# MCU.net
KiCad netlist of a schematic drawn in Altium Designer
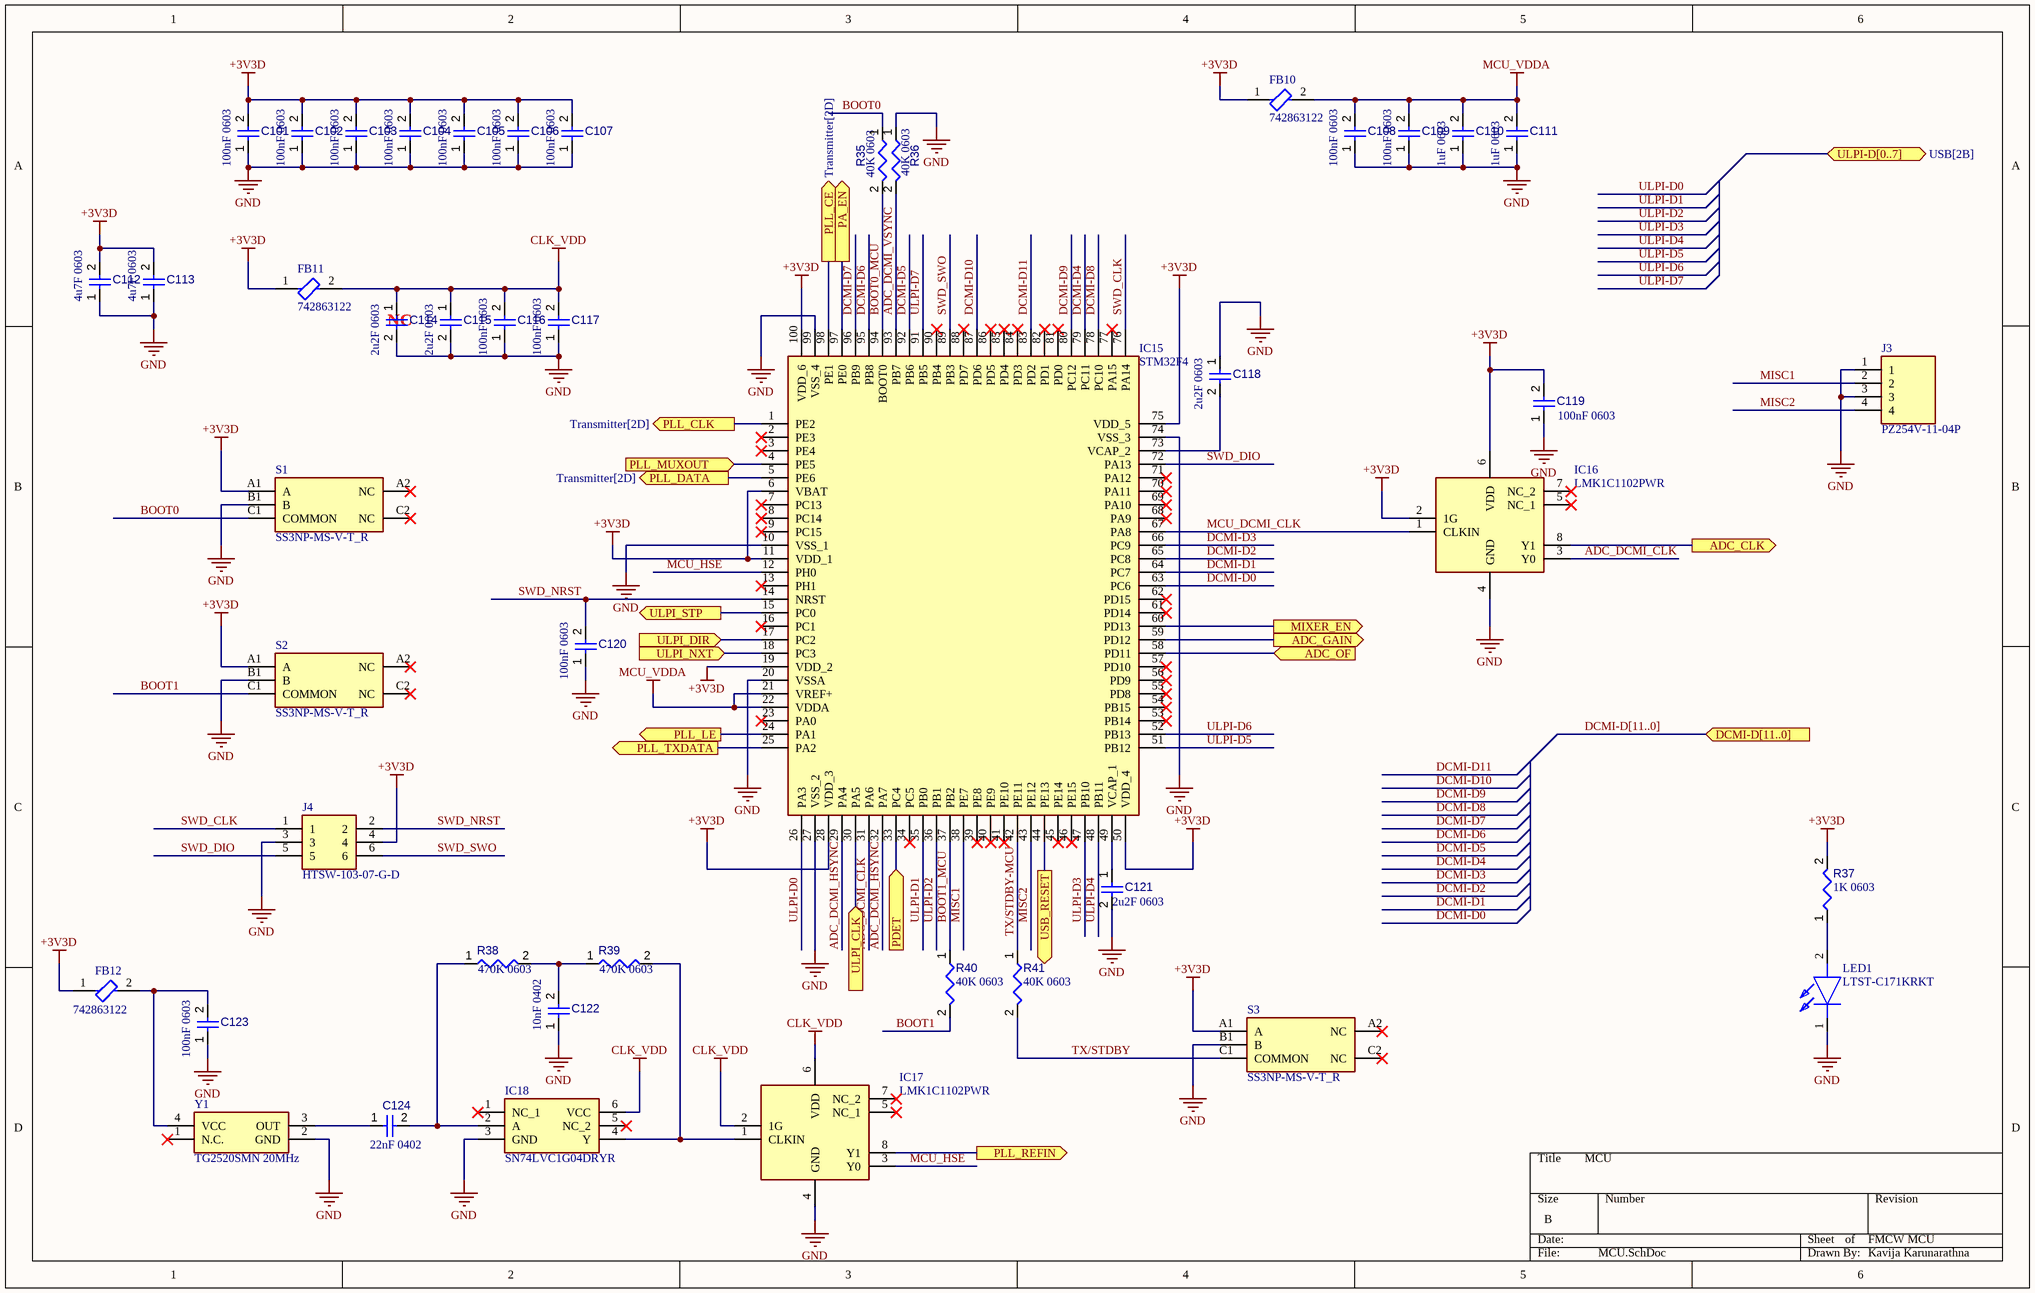
[diagram p0: MCU.SchDoc]

(export (version "E")
  (design (tool "Eeschema 10.0.6"))
  (components
    (comp (ref "C101")
      (value "100nF 0603")
      (footprint "CAPC0603(1608)100_L")
      (description "Chip Capacitor, 1µF +/-0.1%, 25V, 0603, Thickness 1 mm")
      (fields (field (name "TOLERANCE") "20%") (field (name "MANUFACTURER PART NO") "0603X104K250CT"))
      (libsource (lib "Kavija Karunarathna") (part "CAP-NP-2"))
    )
    (comp (ref "C102")
      (value "100nF 0603")
      (footprint "CAPC0603(1608)100_L")
      (description "Chip Capacitor, 1µF +/-0.1%, 25V, 0603, Thickness 1 mm")
      (fields (field (name "TOLERANCE") "20%") (field (name "MANUFACTURER PART NO") "0603X104K250CT"))
      (libsource (lib "Kavija Karunarathna") (part "CAP-NP-2"))
    )
    (comp (ref "C103")
      (value "100nF 0603")
      (footprint "CAPC0603(1608)100_L")
      (description "Chip Capacitor, 1µF +/-0.1%, 25V, 0603, Thickness 1 mm")
      (fields (field (name "TOLERANCE") "20%") (field (name "MANUFACTURER PART NO") "0603X104K250CT"))
      (libsource (lib "Kavija Karunarathna") (part "CAP-NP-2"))
    )
    (comp (ref "C104")
      (value "100nF 0603")
      (footprint "CAPC0603(1608)100_L")
      (description "Chip Capacitor, 1µF +/-0.1%, 25V, 0603, Thickness 1 mm")
      (fields (field (name "TOLERANCE") "20%") (field (name "MANUFACTURER PART NO") "0603X104K250CT"))
      (libsource (lib "Kavija Karunarathna") (part "CAP-NP-2"))
    )
    (comp (ref "C105")
      (value "100nF 0603")
      (footprint "CAPC0603(1608)100_L")
      (description "Chip Capacitor, 1µF +/-0.1%, 25V, 0603, Thickness 1 mm")
      (fields (field (name "TOLERANCE") "20%") (field (name "MANUFACTURER PART NO") "0603X104K250CT"))
      (libsource (lib "Kavija Karunarathna") (part "CAP-NP-2"))
    )
    (comp (ref "C106")
      (value "100nF 0603")
      (footprint "CAPC0603(1608)100_L")
      (description "Chip Capacitor, 1µF +/-0.1%, 25V, 0603, Thickness 1 mm")
      (fields (field (name "TOLERANCE") "20%") (field (name "MANUFACTURER PART NO") "0603X104K250CT"))
      (libsource (lib "Kavija Karunarathna") (part "CAP-NP-2"))
    )
    (comp (ref "C107")
      (value "100nF 0603")
      (footprint "CAPC0603(1608)100_L")
      (description "Chip Capacitor, 1µF +/-0.1%, 25V, 0603, Thickness 1 mm")
      (fields (field (name "TOLERANCE") "20%") (field (name "MANUFACTURER PART NO") "0603X104K250CT"))
      (libsource (lib "Kavija Karunarathna") (part "CAP-NP-2"))
    )
    (comp (ref "C108")
      (value "100nF 0603")
      (footprint "CAPC0603(1608)100_L")
      (description "Chip Capacitor, 1µF +/-0.1%, 25V, 0603, Thickness 1 mm")
      (fields (field (name "TOLERANCE") "20%") (field (name "MANUFACTURER PART NO") "0603X104K250CT"))
      (libsource (lib "Kavija Karunarathna") (part "CAP-NP-2"))
    )
    (comp (ref "C109")
      (value "100nF 0603")
      (footprint "CAPC0603(1608)100_L")
      (description "Chip Capacitor, 1µF +/-0.1%, 25V, 0603, Thickness 1 mm")
      (fields (field (name "TOLERANCE") "20%") (field (name "MANUFACTURER PART NO") "0603X104K250CT"))
      (libsource (lib "Kavija Karunarathna") (part "CAP-NP-2"))
    )
    (comp (ref "C110")
      (value "1uF 0603")
      (footprint "CAPC0603(1608)100_L")
      (description "Chip Capacitor, 1µF +/-0.1%, 25V, 0603, Thickness 1 mm")
      (fields (field (name "TOLERANCE") "20%") (field (name "MANUFACTURER PART NO") "0603YC105KAZ2A"))
      (libsource (lib "Kavija Karunarathna") (part "CAP-NP-2"))
    )
    (comp (ref "C111")
      (value "1uF 0603")
      (footprint "CAPC0603(1608)100_L")
      (description "Chip Capacitor, 1µF +/-0.1%, 25V, 0603, Thickness 1 mm")
      (fields (field (name "TOLERANCE") "20%") (field (name "MANUFACTURER PART NO") "0603YC105KAZ2A"))
      (libsource (lib "Kavija Karunarathna") (part "CAP-NP-2"))
    )
    (comp (ref "C112")
      (value "4u7F 0603")
      (footprint "CAPC0603(1608)100_L")
      (description "Chip Capacitor, 1µF +/-0.1%, 25V, 0603, Thickness 1 mm")
      (fields (field (name "TOLERANCE") "20%") (field (name "MANUFACTURER PART NO") "C0603C475K8PAC7867"))
      (libsource (lib "Kavija Karunarathna") (part "CAP-NP-2"))
    )
    (comp (ref "C113")
      (value "4u7F 0603")
      (footprint "CAPC0603(1608)100_L")
      (description "Chip Capacitor, 1µF +/-0.1%, 25V, 0603, Thickness 1 mm")
      (fields (field (name "TOLERANCE") "20%") (field (name "MANUFACTURER PART NO") "C0603C475K8PAC7867"))
      (libsource (lib "Kavija Karunarathna") (part "CAP-NP-2"))
    )
    (comp (ref "C114")
      (value "2u2F 0603")
      (footprint "CAPC0603(1608)100_L")
      (description "Multilayer Ceramic Capacitors MLCC - SMD/SMT 0603 10nF 16volts X7R 10%")
      (fields (field (name "TOLERANCE") "20%") (field (name "MANUFACTURER PART NO") "VJ0603G225KXQCW1BC"))
      (libsource (lib "Kavija Karunarathna") (part "CAP-NP-2"))
    )
    (comp (ref "C115")
      (value "2u2F 0603")
      (footprint "CAPC0603(1608)100_L")
      (description "Multilayer Ceramic Capacitors MLCC - SMD/SMT 0603 10nF 16volts X7R 10%")
      (fields (field (name "TOLERANCE") "20%") (field (name "MANUFACTURER PART NO") "VJ0603G225KXQCW1BC"))
      (libsource (lib "Kavija Karunarathna") (part "CAP-NP-2"))
    )
    (comp (ref "C116")
      (value "100nF 0603")
      (footprint "CAPC0603(1608)100_L")
      (description "Chip Capacitor, 1µF +/-0.1%, 25V, 0603, Thickness 1 mm")
      (fields (field (name "TOLERANCE") "20%") (field (name "MANUFACTURER PART NO") "0603X104K250CT"))
      (libsource (lib "Kavija Karunarathna") (part "CAP-NP-2"))
    )
    (comp (ref "C117")
      (value "100nF 0603")
      (footprint "CAPC0603(1608)100_L")
      (description "Chip Capacitor, 1µF +/-0.1%, 25V, 0603, Thickness 1 mm")
      (fields (field (name "TOLERANCE") "20%") (field (name "MANUFACTURER PART NO") "0603X104K250CT"))
      (libsource (lib "Kavija Karunarathna") (part "CAP-NP-2"))
    )
    (comp (ref "C118")
      (value "2u2F 0603")
      (footprint "CAPC0603(1608)100_L")
      (description "Multilayer Ceramic Capacitors MLCC - SMD/SMT 0603 10nF 16volts X7R 10%")
      (fields (field (name "TOLERANCE") "20%") (field (name "MANUFACTURER PART NO") "VJ0603G225KXQCW1BC"))
      (libsource (lib "Kavija Karunarathna") (part "CAP-NP-2"))
    )
    (comp (ref "C119")
      (value "100nF 0603")
      (footprint "CAPC0603(1608)100_L")
      (description "Chip Capacitor, 1µF +/-0.1%, 25V, 0603, Thickness 1 mm")
      (fields (field (name "TOLERANCE") "20%") (field (name "MANUFACTURER PART NO") "0603X104K250CT"))
      (libsource (lib "Kavija Karunarathna") (part "CAP-NP-2"))
    )
    (comp (ref "C120")
      (value "100nF 0603")
      (footprint "CAPC0603(1608)100_L")
      (description "Chip Capacitor, 1µF +/-0.1%, 25V, 0603, Thickness 1 mm")
      (fields (field (name "TOLERANCE") "20%") (field (name "MANUFACTURER PART NO") "0603X104K250CT"))
      (libsource (lib "Kavija Karunarathna") (part "CAP-NP-2"))
    )
    (comp (ref "C121")
      (value "2u2F 0603")
      (footprint "CAPC0603(1608)100_L")
      (description "Multilayer Ceramic Capacitors MLCC - SMD/SMT 0603 10nF 16volts X7R 10%")
      (fields (field (name "TOLERANCE") "20%") (field (name "MANUFACTURER PART NO") "VJ0603G225KXQCW1BC"))
      (libsource (lib "Kavija Karunarathna") (part "CAP-NP-2"))
    )
    (comp (ref "C122")
      (value "10nF 0402")
      (footprint "CAPC0402(1005)60_L")
      (description "Multilayer Ceramic Capacitors MLCC - SMD/SMT 50 V 10 pF C0G 0402 1%")
      (fields (field (name "TOLERANCE") "20%") (field (name "MANUFACTURER PART NO") "VJ0402Y103JXJAC"))
      (libsource (lib "Kavija Karunarathna") (part "CAP-NP-2"))
    )
    (comp (ref "C123")
      (value "100nF 0603")
      (footprint "CAPC0603(1608)100_L")
      (description "Chip Capacitor, 1µF +/-0.1%, 25V, 0603, Thickness 1 mm")
      (fields (field (name "TOLERANCE") "20%") (field (name "MANUFACTURER PART NO") "0603X104K250CT"))
      (libsource (lib "Kavija Karunarathna") (part "CAP-NP-2"))
    )
    (comp (ref "C124")
      (value "22nF 0402")
      (footprint "CAPC0402(1005)60_L")
      (description "Multilayer Ceramic Capacitors MLCC - SMD/SMT 50 V 3 pF 0.1 pF C0G (NP0) 0402 - 55 C + 125 C")
      (fields (field (name "TOLERANCE") "20%") (field (name "MANUFACTURER PART NO") "GRM155R71E223KA61D"))
      (libsource (lib "Kavija Karunarathna") (part "CAP-NP-2"))
    )
    (comp (ref "FB10")
      (value "742863122")
      (footprint "FB-0603")
      (description "FERRITE BEAD 0603")
      (fields (field (name "MOUSER PART NO") "710-742863122"))
      (libsource (lib "SchLib") (part "742792662-FB"))
    )
    (comp (ref "FB11")
      (value "742863122")
      (footprint "FB-0603")
      (description "FERRITE BEAD 0603")
      (fields (field (name "MOUSER PART NO") "710-742863122"))
      (libsource (lib "SchLib") (part "742792662-FB"))
    )
    (comp (ref "FB12")
      (value "742863122")
      (footprint "FB-0603")
      (description "FERRITE BEAD 0603")
      (fields (field (name "MOUSER PART NO") "710-742863122"))
      (libsource (lib "SchLib") (part "742792662-FB"))
    )
    (comp (ref "IC15")
      (value "STM32F4")
      (footprint "SamacSys:QFP50P1600X1600X160-100N")
      (description "Integrated Circuit")
      (fields
        (field (name "MANUFACTURER PART NO") "STM32F429VET6TR")
        (field (name "MOUSER PART NO") "511-STM32F429VET6TR")
      )
      (libsource (lib "SchLib") (part "STM32F429VET6TR"))
    )
    (comp (ref "IC16")
      (value "LMK1C1102PWR")
      (footprint "SOP65P640X120-8N")
      (description "Integrated Circuit")
      (fields (field (name "MOUSER PART NO") "595-LMK1C1102PWR"))
      (libsource (lib "SchLib") (part "LMK1C1102PWR"))
    )
    (comp (ref "IC17")
      (value "LMK1C1102PWR")
      (footprint "SOP65P640X120-8N")
      (description "Integrated Circuit")
      (fields (field (name "MOUSER PART NO") "595-LMK1C1102PWR"))
      (libsource (lib "SchLib") (part "LMK1C1102PWR"))
    )
    (comp (ref "IC18")
      (value "SN74LVC1G04DRYR")
      (footprint "TPS3420DDRYR")
      (description "Integrated Circuit")
      (fields
        (field (name "MANUFACTURER PART NO") "SN74LVC1G04DRY2")
        (field (name "MOUSER PART NO") "595-SN74LVC1G04DRY2")
      )
      (libsource (lib "SchLib") (part "SN74LVC1G04DRYR"))
    )
    (comp (ref "J3")
      (value "PZ254V-11-04P")
      (footprint "SamacSys:HDRV4W64P0X254_1X4_1016X250X890P")
      (description "Connector")
      (libsource (lib "*") (part "PZ254V-11-04P"))
    )
    (comp (ref "J4")
      (value "HTSW-103-07-G-D")
      (footprint "HDRV6W64P254_2X3_762X508X838P")
      (description "Connector")
      (fields (field (name "MOUSER PART NO") "200-HTSW10307GD"))
      (libsource (lib "SchLib") (part "HTSW-103-07-G-D"))
    )
    (comp (ref "LED1")
      (value "LTST-C171KRKT")
      (footprint "LEDM2012X90N")
      (description "LED")
      (fields (field (name "MOUSER PART NO") "859-LTST-C171KRKT"))
      (libsource (lib "SchLib") (part "LTST-C171KRKT"))
    )
    (comp (ref "R35")
      (value "40K 0603")
      (footprint "RESC0603(1608)_L")
      (description "Thin Film Resistors - SMD 0603 40kOhms 0.1% 25 PPM 100mW AECQ200")
      (fields (field (name "POWER") "100mW") (field (name "TOLERANCE") "5%"))
      (libsource (lib "Kavija Karunarathna") (part "120R3J"))
    )
    (comp (ref "R36")
      (value "40K 0603")
      (footprint "RESC0603(1608)_L")
      (description "Thin Film Resistors - SMD 0603 40kOhms 0.1% 25 PPM 100mW AECQ200")
      (fields (field (name "POWER") "100mW") (field (name "TOLERANCE") "5%"))
      (libsource (lib "Kavija Karunarathna") (part "120R3J"))
    )
    (comp (ref "R37")
      (value "1K 0603")
      (footprint "RESC0603(1608)_L")
      (description "Thin Film Resistors - SMD RN 0603 8K06 0.1% 10PPM")
      (fields (field (name "POWER") "100mW") (field (name "TOLERANCE") "5%"))
      (libsource (lib "Kavija Karunarathna") (part "120R3J"))
    )
    (comp (ref "R38")
      (value "470K 0603")
      (footprint "RESC0603(1608)_L")
      (description "Thick Film Resistors - SMD General Purpose Chip Resistor 0603, 200Ohms, 1%, 1/10W")
      (fields (field (name "POWER") "100mW") (field (name "TOLERANCE") "5%"))
      (libsource (lib "Kavija Karunarathna") (part "120R3J"))
    )
    (comp (ref "R39")
      (value "470K 0603")
      (footprint "RESC0603(1608)_L")
      (description "Thick Film Resistors - SMD General Purpose Chip Resistor 0603, 200Ohms, 1%, 1/10W")
      (fields (field (name "POWER") "100mW") (field (name "TOLERANCE") "5%"))
      (libsource (lib "Kavija Karunarathna") (part "120R3J"))
    )
    (comp (ref "R40")
      (value "40K 0603")
      (footprint "RESC0603(1608)_L")
      (description "Thin Film Resistors - SMD 0603 40kOhms 0.1% 25 PPM 100mW AECQ200")
      (fields (field (name "POWER") "100mW") (field (name "TOLERANCE") "5%"))
      (libsource (lib "Kavija Karunarathna") (part "120R3J"))
    )
    (comp (ref "R41")
      (value "40K 0603")
      (footprint "RESC0603(1608)_L")
      (description "Thin Film Resistors - SMD 0603 40kOhms 0.1% 25 PPM 100mW AECQ200")
      (fields (field (name "POWER") "100mW") (field (name "TOLERANCE") "5%"))
      (libsource (lib "Kavija Karunarathna") (part "120R3J"))
    )
    (comp (ref "S1")
      (value "SS3NP-MS-V-T_R")
      (footprint "SS3NPMSVTR")
      (description "Switch")
      (fields
        (field (name "MANUFACTURER PART NO") "SS3NP-MS-V-T/R")
        (field (name "MOUSER PART NO") "113-SS3NPMSVT/R")
      )
      (libsource (lib "SchLib") (part "SS3NP-MS-V-T_R"))
    )
    (comp (ref "S2")
      (value "SS3NP-MS-V-T_R")
      (footprint "SS3NPMSVTR")
      (description "Switch")
      (fields
        (field (name "MANUFACTURER PART NO") "SS3NP-MS-V-T/R")
        (field (name "MOUSER PART NO") "113-SS3NPMSVT/R")
      )
      (libsource (lib "SchLib") (part "SS3NP-MS-V-T_R"))
    )
    (comp (ref "S3")
      (value "SS3NP-MS-V-T_R")
      (footprint "SS3NPMSVTR")
      (description "Switch")
      (fields
        (field (name "MANUFACTURER PART NO") "SS3NP-MS-V-T/R")
        (field (name "MOUSER PART NO") "113-SS3NPMSVT/R")
      )
      (libsource (lib "SchLib") (part "SS3NP-MS-V-T_R"))
    )
    (comp (ref "Y1")
      (value "TG2520SMN 20MHz")
      (footprint "TG2520SMN200000MECGNNM3")
      (description "Crystal or Oscillator")
      (fields
        (field (name "MANUFACTURER PART NO") "TG2520SMN 20.0000M-MCGNNM3")
        (field (name "MOUSER PART NO") "732-TG252S2MCGNNM3")
      )
      (libsource (lib "SchLib") (part "TG2520SMN 20MHz"))
    )
  )
  (nets
    (net (code "1") (name "+3V3D") (class "Default")
      (node (ref "C101") (pin "2") (pinfunction "2_2") (pintype "passive"))
      (node (ref "C102") (pin "2") (pinfunction "2_2") (pintype "passive"))
      (node (ref "C103") (pin "2") (pinfunction "2_2") (pintype "passive"))
      (node (ref "C104") (pin "2") (pinfunction "2_2") (pintype "passive"))
      (node (ref "C105") (pin "2") (pinfunction "2_2") (pintype "passive"))
      (node (ref "C106") (pin "2") (pinfunction "2_2") (pintype "passive"))
      (node (ref "C107") (pin "2") (pinfunction "2_2") (pintype "passive"))
      (node (ref "C112") (pin "2") (pinfunction "2_2") (pintype "passive"))
      (node (ref "C113") (pin "2") (pinfunction "2_2") (pintype "passive"))
      (node (ref "C119") (pin "2") (pinfunction "2_2") (pintype "passive"))
      (node (ref "FB10") (pin "1") (pinfunction "1_1") (pintype "passive"))
      (node (ref "FB11") (pin "1") (pinfunction "1_1") (pintype "passive"))
      (node (ref "FB12") (pin "1") (pinfunction "1_1") (pintype "passive"))
      (node (ref "IC15") (pin "100") (pinfunction "VDD_6_100") (pintype "passive"))
      (node (ref "IC15") (pin "11") (pinfunction "VDD_1_11") (pintype "passive"))
      (node (ref "IC15") (pin "19") (pinfunction "VDD_2_19") (pintype "passive"))
      (node (ref "IC15") (pin "28") (pinfunction "VDD_3_28") (pintype "passive"))
      (node (ref "IC15") (pin "50") (pinfunction "VDD_4_50") (pintype "passive"))
      (node (ref "IC15") (pin "6") (pinfunction "VBAT_6") (pintype "passive"))
      (node (ref "IC15") (pin "75") (pinfunction "VDD_5_75") (pintype "passive"))
      (node (ref "IC16") (pin "2") (pinfunction "1G_2") (pintype "passive"))
      (node (ref "IC16") (pin "6") (pinfunction "VDD_6") (pintype "passive"))
      (node (ref "J4") (pin "4") (pinfunction "4_4") (pintype "passive"))
      (node (ref "R37") (pin "2") (pinfunction "2_2") (pintype "passive"))
      (node (ref "S1") (pin "A1") (pinfunction "A_A1") (pintype "passive"))
      (node (ref "S2") (pin "A1") (pinfunction "A_A1") (pintype "passive"))
      (node (ref "S3") (pin "A1") (pinfunction "A_A1") (pintype "passive"))
    )
    (net (code "2") (name "/ADC_CLK") (class "Default")
      (node (ref "IC16") (pin "8") (pinfunction "Y1_8") (pintype "passive"))
    )
    (net (code "3") (name "/ADC_DCMI_CLK") (class "Default")
      (node (ref "IC15") (pin "31") (pinfunction "PA6_31") (pintype "passive"))
      (node (ref "IC16") (pin "3") (pinfunction "Y0_3") (pintype "passive"))
    )
    (net (code "4") (name "/ADC_DCMI_HSYNC") (class "Default")
      (node (ref "IC15") (pin "29") (pinfunction "PA4_29") (pintype "passive"))
      (node (ref "IC15") (pin "32") (pinfunction "PA7_32") (pintype "passive"))
    )
    (net (code "5") (name "/ADC_DCMI_VSYNC") (class "Default")
      (node (ref "IC15") (pin "93") (pinfunction "PB7_93") (pintype "passive"))
      (node (ref "R36") (pin "2") (pinfunction "2_2") (pintype "passive"))
    )
    (net (code "6") (name "/ADC_GAIN") (class "Default")
      (node (ref "IC15") (pin "59") (pinfunction "PD12_59") (pintype "passive"))
    )
    (net (code "7") (name "/ADC_OF") (class "Default")
      (node (ref "IC15") (pin "58") (pinfunction "PD11_58") (pintype "passive"))
    )
    (net (code "8") (name "/BOOT0") (class "Default")
      (node (ref "R35") (pin "1") (pinfunction "1_1") (pintype "passive"))
      (node (ref "S1") (pin "C1") (pinfunction "COMMON_C1") (pintype "passive"))
    )
    (net (code "9") (name "/BOOT0_MCU") (class "Default")
      (node (ref "IC15") (pin "94") (pinfunction "BOOT0_94") (pintype "passive"))
      (node (ref "R35") (pin "2") (pinfunction "2_2") (pintype "passive"))
    )
    (net (code "10") (name "/BOOT1") (class "Default")
      (node (ref "R40") (pin "2") (pinfunction "2_2") (pintype "passive"))
      (node (ref "S2") (pin "C1") (pinfunction "COMMON_C1") (pintype "passive"))
    )
    (net (code "11") (name "/BOOT1_MCU") (class "Default")
      (node (ref "IC15") (pin "37") (pinfunction "PB2_37") (pintype "passive"))
      (node (ref "R40") (pin "1") (pinfunction "1_1") (pintype "passive"))
    )
    (net (code "12") (name "/DCMI-D0") (class "Default")
      (node (ref "IC15") (pin "63") (pinfunction "PC6_63") (pintype "passive"))
    )
    (net (code "13") (name "/DCMI-D1") (class "Default")
      (node (ref "IC15") (pin "64") (pinfunction "PC7_64") (pintype "passive"))
    )
    (net (code "14") (name "/DCMI-D2") (class "Default")
      (node (ref "IC15") (pin "65") (pinfunction "PC8_65") (pintype "passive"))
    )
    (net (code "15") (name "/DCMI-D3") (class "Default")
      (node (ref "IC15") (pin "66") (pinfunction "PC9_66") (pintype "passive"))
    )
    (net (code "16") (name "/DCMI-D4") (class "Default")
      (node (ref "IC15") (pin "79") (pinfunction "PC11_79") (pintype "passive"))
    )
    (net (code "17") (name "/DCMI-D5") (class "Default")
      (node (ref "IC15") (pin "92") (pinfunction "PB6_92") (pintype "passive"))
    )
    (net (code "18") (name "/DCMI-D6") (class "Default")
      (node (ref "IC15") (pin "95") (pinfunction "PB8_95") (pintype "passive"))
    )
    (net (code "19") (name "/DCMI-D7") (class "Default")
      (node (ref "IC15") (pin "96") (pinfunction "PB9_96") (pintype "passive"))
    )
    (net (code "20") (name "/DCMI-D8") (class "Default")
      (node (ref "IC15") (pin "78") (pinfunction "PC10_78") (pintype "passive"))
    )
    (net (code "21") (name "/DCMI-D9") (class "Default")
      (node (ref "IC15") (pin "80") (pinfunction "PC12_80") (pintype "passive"))
    )
    (net (code "22") (name "/DCMI-D10") (class "Default")
      (node (ref "IC15") (pin "87") (pinfunction "PD6_87") (pintype "passive"))
    )
    (net (code "23") (name "/DCMI-D11") (class "Default")
      (node (ref "IC15") (pin "83") (pinfunction "PD2_83") (pintype "passive"))
    )
    (net (code "25") (name "/MCU_DCMI_CLK") (class "Default")
      (node (ref "IC15") (pin "67") (pinfunction "PA8_67") (pintype "passive"))
      (node (ref "IC16") (pin "1") (pinfunction "CLKIN_1") (pintype "passive"))
    )
    (net (code "26") (name "/MCU_HSE") (class "Default")
      (node (ref "IC15") (pin "12") (pinfunction "PH0_12") (pintype "passive"))
      (node (ref "IC17") (pin "3") (pinfunction "Y0_3") (pintype "passive"))
    )
    (net (code "27") (name "/MISC1") (class "Default")
      (node (ref "IC15") (pin "38") (pinfunction "PE7_38") (pintype "passive"))
      (node (ref "J3") (pin "2") (pinfunction "2_2") (pintype "passive"))
    )
    (net (code "28") (name "/MISC2") (class "Default")
      (node (ref "IC15") (pin "43") (pinfunction "PE12_43") (pintype "passive"))
      (node (ref "J3") (pin "4") (pinfunction "4_4") (pintype "passive"))
    )
    (net (code "29") (name "/MIXER_EN") (class "Default")
      (node (ref "IC15") (pin "60") (pinfunction "PD13_60") (pintype "passive"))
    )
    (net (code "30") (name "/PA_EN") (class "Default")
      (node (ref "IC15") (pin "97") (pinfunction "PE0_97") (pintype "passive"))
    )
    (net (code "31") (name "/PDET") (class "Default")
      (node (ref "IC15") (pin "33") (pinfunction "PC4_33") (pintype "passive"))
    )
    (net (code "32") (name "/PLL_CE") (class "Default")
      (node (ref "IC15") (pin "98") (pinfunction "PE1_98") (pintype "passive"))
    )
    (net (code "33") (name "/PLL_CLK") (class "Default")
      (node (ref "IC15") (pin "1") (pinfunction "PE2_1") (pintype "passive"))
    )
    (net (code "34") (name "/PLL_DATA") (class "Default")
      (node (ref "IC15") (pin "5") (pinfunction "PE6_5") (pintype "passive"))
    )
    (net (code "35") (name "/PLL_LE") (class "Default")
      (node (ref "IC15") (pin "24") (pinfunction "PA1_24") (pintype "passive"))
    )
    (net (code "36") (name "/PLL_MUXOUT") (class "Default")
      (node (ref "IC15") (pin "4") (pinfunction "PE5_4") (pintype "passive"))
    )
    (net (code "37") (name "/PLL_REFIN") (class "Default")
      (node (ref "IC17") (pin "8") (pinfunction "Y1_8") (pintype "passive"))
    )
    (net (code "38") (name "/PLL_TXDATA") (class "Default")
      (node (ref "IC15") (pin "25") (pinfunction "PA2_25") (pintype "passive"))
    )
    (net (code "39") (name "/SWD_CLK") (class "Default")
      (node (ref "IC15") (pin "76") (pinfunction "PA14_76") (pintype "passive"))
      (node (ref "J4") (pin "1") (pinfunction "1_1") (pintype "passive"))
    )
    (net (code "40") (name "/SWD_DIO") (class "Default")
      (node (ref "IC15") (pin "72") (pinfunction "PA13_72") (pintype "passive"))
      (node (ref "J4") (pin "5") (pinfunction "5_5") (pintype "passive"))
    )
    (net (code "41") (name "/SWD_NRST") (class "Default")
      (node (ref "C120") (pin "2") (pinfunction "2_2") (pintype "passive"))
      (node (ref "IC15") (pin "14") (pinfunction "NRST_14") (pintype "passive"))
      (node (ref "J4") (pin "2") (pinfunction "2_2") (pintype "passive"))
    )
    (net (code "42") (name "/SWD_SWO") (class "Default")
      (node (ref "IC15") (pin "89") (pinfunction "PB3_89") (pintype "passive"))
      (node (ref "J4") (pin "6") (pinfunction "6_6") (pintype "passive"))
    )
    (net (code "43") (name "/TX{slash}STDBY") (class "Default")
      (node (ref "R41") (pin "2") (pinfunction "2_2") (pintype "passive"))
      (node (ref "S3") (pin "C1") (pinfunction "COMMON_C1") (pintype "passive"))
    )
    (net (code "44") (name "/TX{slash}STDBY-MCU") (class "Default")
      (node (ref "IC15") (pin "42") (pinfunction "PE11_42") (pintype "passive"))
      (node (ref "R41") (pin "1") (pinfunction "1_1") (pintype "passive"))
    )
    (net (code "45") (name "/ULPI-D0") (class "Default")
      (node (ref "IC15") (pin "26") (pinfunction "PA3_26") (pintype "passive"))
    )
    (net (code "46") (name "/ULPI-D1") (class "Default")
      (node (ref "IC15") (pin "35") (pinfunction "PB0_35") (pintype "passive"))
    )
    (net (code "47") (name "/ULPI-D2") (class "Default")
      (node (ref "IC15") (pin "36") (pinfunction "PB1_36") (pintype "passive"))
    )
    (net (code "48") (name "/ULPI-D3") (class "Default")
      (node (ref "IC15") (pin "47") (pinfunction "PB10_47") (pintype "passive"))
    )
    (net (code "49") (name "/ULPI-D4") (class "Default")
      (node (ref "IC15") (pin "48") (pinfunction "PB11_48") (pintype "passive"))
    )
    (net (code "50") (name "/ULPI-D5") (class "Default")
      (node (ref "IC15") (pin "51") (pinfunction "PB12_51") (pintype "passive"))
    )
    (net (code "51") (name "/ULPI-D6") (class "Default")
      (node (ref "IC15") (pin "52") (pinfunction "PB13_52") (pintype "passive"))
    )
    (net (code "52") (name "/ULPI-D7") (class "Default")
      (node (ref "IC15") (pin "91") (pinfunction "PB5_91") (pintype "passive"))
    )
    (net (code "54") (name "/ULPI_CLK") (class "Default")
      (node (ref "IC15") (pin "30") (pinfunction "PA5_30") (pintype "passive"))
    )
    (net (code "55") (name "/ULPI_DIR") (class "Default")
      (node (ref "IC15") (pin "17") (pinfunction "PC2_17") (pintype "passive"))
    )
    (net (code "56") (name "/ULPI_NXT") (class "Default")
      (node (ref "IC15") (pin "18") (pinfunction "PC3_18") (pintype "passive"))
    )
    (net (code "57") (name "/ULPI_STP") (class "Default")
      (node (ref "IC15") (pin "15") (pinfunction "PC0_15") (pintype "passive"))
    )
    (net (code "58") (name "/USB_RESET") (class "Default")
      (node (ref "IC15") (pin "44") (pinfunction "PE13_44") (pintype "passive"))
    )
    (net (code "59") (name "CLK_VDD") (class "Default")
      (node (ref "C114") (pin "1") (pinfunction "1_1") (pintype "passive"))
      (node (ref "C115") (pin "1") (pinfunction "1_1") (pintype "passive"))
      (node (ref "C116") (pin "2") (pinfunction "2_2") (pintype "passive"))
      (node (ref "C117") (pin "2") (pinfunction "2_2") (pintype "passive"))
      (node (ref "FB11") (pin "2") (pinfunction "2_2") (pintype "passive"))
      (node (ref "IC17") (pin "2") (pinfunction "1G_2") (pintype "passive"))
      (node (ref "IC17") (pin "6") (pinfunction "VDD_6") (pintype "passive"))
      (node (ref "IC18") (pin "6") (pinfunction "VCC_6") (pintype "passive"))
    )
    (net (code "60") (name "GND") (class "Default")
      (node (ref "C101") (pin "1") (pinfunction "1_1") (pintype "passive"))
      (node (ref "C102") (pin "1") (pinfunction "1_1") (pintype "passive"))
      (node (ref "C103") (pin "1") (pinfunction "1_1") (pintype "passive"))
      (node (ref "C104") (pin "1") (pinfunction "1_1") (pintype "passive"))
      (node (ref "C105") (pin "1") (pinfunction "1_1") (pintype "passive"))
      (node (ref "C106") (pin "1") (pinfunction "1_1") (pintype "passive"))
      (node (ref "C107") (pin "1") (pinfunction "1_1") (pintype "passive"))
      (node (ref "C108") (pin "1") (pinfunction "1_1") (pintype "passive"))
      (node (ref "C109") (pin "1") (pinfunction "1_1") (pintype "passive"))
      (node (ref "C110") (pin "1") (pinfunction "1_1") (pintype "passive"))
      (node (ref "C111") (pin "1") (pinfunction "1_1") (pintype "passive"))
      (node (ref "C112") (pin "1") (pinfunction "1_1") (pintype "passive"))
      (node (ref "C113") (pin "1") (pinfunction "1_1") (pintype "passive"))
      (node (ref "C114") (pin "2") (pinfunction "2_2") (pintype "passive"))
      (node (ref "C115") (pin "2") (pinfunction "2_2") (pintype "passive"))
      (node (ref "C116") (pin "1") (pinfunction "1_1") (pintype "passive"))
      (node (ref "C117") (pin "1") (pinfunction "1_1") (pintype "passive"))
      (node (ref "C118") (pin "1") (pinfunction "1_1") (pintype "passive"))
      (node (ref "C119") (pin "1") (pinfunction "1_1") (pintype "passive"))
      (node (ref "C120") (pin "1") (pinfunction "1_1") (pintype "passive"))
      (node (ref "C121") (pin "2") (pinfunction "2_2") (pintype "passive"))
      (node (ref "C122") (pin "1") (pinfunction "1_1") (pintype "passive"))
      (node (ref "C123") (pin "1") (pinfunction "1_1") (pintype "passive"))
      (node (ref "IC15") (pin "10") (pinfunction "VSS_1_10") (pintype "passive"))
      (node (ref "IC15") (pin "20") (pinfunction "VSSA_20") (pintype "passive"))
      (node (ref "IC15") (pin "27") (pinfunction "VSS_2_27") (pintype "passive"))
      (node (ref "IC15") (pin "74") (pinfunction "VSS_3_74") (pintype "passive"))
      (node (ref "IC15") (pin "99") (pinfunction "VSS_4_99") (pintype "passive"))
      (node (ref "IC16") (pin "4") (pinfunction "GND_4") (pintype "passive"))
      (node (ref "IC17") (pin "4") (pinfunction "GND_4") (pintype "passive"))
      (node (ref "IC18") (pin "3") (pinfunction "GND_3") (pintype "passive"))
      (node (ref "J3") (pin "1") (pinfunction "1_1") (pintype "passive"))
      (node (ref "J3") (pin "3") (pinfunction "3_3") (pintype "passive"))
      (node (ref "J4") (pin "3") (pinfunction "3_3") (pintype "passive"))
      (node (ref "LED1") (pin "1") (pinfunction "K_1") (pintype "passive"))
      (node (ref "R36") (pin "1") (pinfunction "1_1") (pintype "passive"))
      (node (ref "S1") (pin "B1") (pinfunction "B_B1") (pintype "passive"))
      (node (ref "S2") (pin "B1") (pinfunction "B_B1") (pintype "passive"))
      (node (ref "S3") (pin "B1") (pinfunction "B_B1") (pintype "passive"))
      (node (ref "Y1") (pin "2") (pinfunction "GND_2") (pintype "passive"))
    )
    (net (code "61") (name "MCU_VDDA") (class "Default")
      (node (ref "C108") (pin "2") (pinfunction "2_2") (pintype "passive"))
      (node (ref "C109") (pin "2") (pinfunction "2_2") (pintype "passive"))
      (node (ref "C110") (pin "2") (pinfunction "2_2") (pintype "passive"))
      (node (ref "C111") (pin "2") (pinfunction "2_2") (pintype "passive"))
      (node (ref "FB10") (pin "2") (pinfunction "2_2") (pintype "passive"))
      (node (ref "IC15") (pin "21") (pinfunction "VREF+_21") (pintype "passive"))
      (node (ref "IC15") (pin "22") (pinfunction "VDDA_22") (pintype "passive"))
    )
    (net (code "62") (name "Net-(C122-Pad2)") (class "Default")
      (node (ref "C122") (pin "2") (pinfunction "2_2") (pintype "passive"))
      (node (ref "R38") (pin "2") (pinfunction "2_2") (pintype "passive"))
      (node (ref "R39") (pin "1") (pinfunction "1_1") (pintype "passive"))
    )
    (net (code "63") (name "Net-(IC15-VCAP_1)") (class "Default")
      (node (ref "C121") (pin "1") (pinfunction "1_1") (pintype "passive"))
      (node (ref "IC15") (pin "49") (pinfunction "VCAP_1_49") (pintype "passive"))
    )
    (net (code "64") (name "Net-(IC15-VCAP_2)") (class "Default")
      (node (ref "C118") (pin "2") (pinfunction "2_2") (pintype "passive"))
      (node (ref "IC15") (pin "73") (pinfunction "VCAP_2_73") (pintype "passive"))
    )
    (net (code "65") (name "Net-(IC17-CLKIN)") (class "Default")
      (node (ref "IC17") (pin "1") (pinfunction "CLKIN_1") (pintype "passive"))
      (node (ref "IC18") (pin "4") (pinfunction "Y_4") (pintype "passive"))
      (node (ref "R39") (pin "2") (pinfunction "2_2") (pintype "passive"))
    )
    (net (code "66") (name "Net-(IC18-A)") (class "Default")
      (node (ref "C124") (pin "2") (pinfunction "2_2") (pintype "passive"))
      (node (ref "IC18") (pin "2") (pinfunction "A_2") (pintype "passive"))
      (node (ref "R38") (pin "1") (pinfunction "1_1") (pintype "passive"))
    )
    (net (code "67") (name "Net-(LED1-A)") (class "Default")
      (node (ref "LED1") (pin "2") (pinfunction "A_2") (pintype "passive"))
      (node (ref "R37") (pin "1") (pinfunction "1_1") (pintype "passive"))
    )
    (net (code "68") (name "Net-(Y1-OUT)") (class "Default")
      (node (ref "C124") (pin "1") (pinfunction "1_1") (pintype "passive"))
      (node (ref "Y1") (pin "3") (pinfunction "OUT_3") (pintype "passive"))
    )
    (net (code "69") (name "Net-(Y1-VCC)") (class "Default")
      (node (ref "C123") (pin "2") (pinfunction "2_2") (pintype "passive"))
      (node (ref "FB12") (pin "2") (pinfunction "2_2") (pintype "passive"))
      (node (ref "Y1") (pin "4") (pinfunction "VCC_4") (pintype "passive"))
    )
    (net (code "70") (name "unconnected-(IC15-PA0-Pad23)") (class "Default")
      (node (ref "IC15") (pin "23") (pinfunction "PA0_23") (pintype "passive+no_connect"))
    )
    (net (code "71") (name "unconnected-(IC15-PA9-Pad68)") (class "Default")
      (node (ref "IC15") (pin "68") (pinfunction "PA9_68") (pintype "passive+no_connect"))
    )
    (net (code "72") (name "unconnected-(IC15-PA10-Pad69)") (class "Default")
      (node (ref "IC15") (pin "69") (pinfunction "PA10_69") (pintype "passive+no_connect"))
    )
    (net (code "73") (name "unconnected-(IC15-PA11-Pad70)") (class "Default")
      (node (ref "IC15") (pin "70") (pinfunction "PA11_70") (pintype "passive+no_connect"))
    )
    (net (code "74") (name "unconnected-(IC15-PA12-Pad71)") (class "Default")
      (node (ref "IC15") (pin "71") (pinfunction "PA12_71") (pintype "passive+no_connect"))
    )
    (net (code "75") (name "unconnected-(IC15-PA15-Pad77)") (class "Default")
      (node (ref "IC15") (pin "77") (pinfunction "PA15_77") (pintype "passive+no_connect"))
    )
    (net (code "76") (name "unconnected-(IC15-PB4-Pad90)") (class "Default")
      (node (ref "IC15") (pin "90") (pinfunction "PB4_90") (pintype "passive+no_connect"))
    )
    (net (code "77") (name "unconnected-(IC15-PB14-Pad53)") (class "Default")
      (node (ref "IC15") (pin "53") (pinfunction "PB14_53") (pintype "passive+no_connect"))
    )
    (net (code "78") (name "unconnected-(IC15-PB15-Pad54)") (class "Default")
      (node (ref "IC15") (pin "54") (pinfunction "PB15_54") (pintype "passive+no_connect"))
    )
    (net (code "79") (name "unconnected-(IC15-PC1-Pad16)") (class "Default")
      (node (ref "IC15") (pin "16") (pinfunction "PC1_16") (pintype "passive+no_connect"))
    )
    (net (code "80") (name "unconnected-(IC15-PC5-Pad34)") (class "Default")
      (node (ref "IC15") (pin "34") (pinfunction "PC5_34") (pintype "passive+no_connect"))
    )
    (net (code "81") (name "unconnected-(IC15-PC13-Pad7)") (class "Default")
      (node (ref "IC15") (pin "7") (pinfunction "PC13_7") (pintype "passive+no_connect"))
    )
    (net (code "82") (name "unconnected-(IC15-PC14-Pad8)") (class "Default")
      (node (ref "IC15") (pin "8") (pinfunction "PC14_8") (pintype "passive+no_connect"))
    )
    (net (code "83") (name "unconnected-(IC15-PC15-Pad9)") (class "Default")
      (node (ref "IC15") (pin "9") (pinfunction "PC15_9") (pintype "passive+no_connect"))
    )
    (net (code "84") (name "unconnected-(IC15-PD0-Pad81)") (class "Default")
      (node (ref "IC15") (pin "81") (pinfunction "PD0_81") (pintype "passive+no_connect"))
    )
    (net (code "85") (name "unconnected-(IC15-PD1-Pad82)") (class "Default")
      (node (ref "IC15") (pin "82") (pinfunction "PD1_82") (pintype "passive+no_connect"))
    )
    (net (code "86") (name "unconnected-(IC15-PD3-Pad84)") (class "Default")
      (node (ref "IC15") (pin "84") (pinfunction "PD3_84") (pintype "passive+no_connect"))
    )
    (net (code "87") (name "unconnected-(IC15-PD4-Pad85)") (class "Default")
      (node (ref "IC15") (pin "85") (pinfunction "PD4_85") (pintype "passive+no_connect"))
    )
    (net (code "88") (name "unconnected-(IC15-PD5-Pad86)") (class "Default")
      (node (ref "IC15") (pin "86") (pinfunction "PD5_86") (pintype "passive+no_connect"))
    )
    (net (code "89") (name "unconnected-(IC15-PD7-Pad88)") (class "Default")
      (node (ref "IC15") (pin "88") (pinfunction "PD7_88") (pintype "passive+no_connect"))
    )
    (net (code "90") (name "unconnected-(IC15-PD8-Pad55)") (class "Default")
      (node (ref "IC15") (pin "55") (pinfunction "PD8_55") (pintype "passive+no_connect"))
    )
    (net (code "91") (name "unconnected-(IC15-PD9-Pad56)") (class "Default")
      (node (ref "IC15") (pin "56") (pinfunction "PD9_56") (pintype "passive+no_connect"))
    )
    (net (code "92") (name "unconnected-(IC15-PD10-Pad57)") (class "Default")
      (node (ref "IC15") (pin "57") (pinfunction "PD10_57") (pintype "passive+no_connect"))
    )
    (net (code "93") (name "unconnected-(IC15-PD14-Pad61)") (class "Default")
      (node (ref "IC15") (pin "61") (pinfunction "PD14_61") (pintype "passive+no_connect"))
    )
    (net (code "94") (name "unconnected-(IC15-PD15-Pad62)") (class "Default")
      (node (ref "IC15") (pin "62") (pinfunction "PD15_62") (pintype "passive+no_connect"))
    )
    (net (code "95") (name "unconnected-(IC15-PE3-Pad2)") (class "Default")
      (node (ref "IC15") (pin "2") (pinfunction "PE3_2") (pintype "passive+no_connect"))
    )
    (net (code "96") (name "unconnected-(IC15-PE4-Pad3)") (class "Default")
      (node (ref "IC15") (pin "3") (pinfunction "PE4_3") (pintype "passive+no_connect"))
    )
    (net (code "97") (name "unconnected-(IC15-PE8-Pad39)") (class "Default")
      (node (ref "IC15") (pin "39") (pinfunction "PE8_39") (pintype "passive+no_connect"))
    )
    (net (code "98") (name "unconnected-(IC15-PE9-Pad40)") (class "Default")
      (node (ref "IC15") (pin "40") (pinfunction "PE9_40") (pintype "passive+no_connect"))
    )
    (net (code "99") (name "unconnected-(IC15-PE10-Pad41)") (class "Default")
      (node (ref "IC15") (pin "41") (pinfunction "PE10_41") (pintype "passive+no_connect"))
    )
    (net (code "100") (name "unconnected-(IC15-PE14-Pad45)") (class "Default")
      (node (ref "IC15") (pin "45") (pinfunction "PE14_45") (pintype "passive+no_connect"))
    )
    (net (code "101") (name "unconnected-(IC15-PE15-Pad46)") (class "Default")
      (node (ref "IC15") (pin "46") (pinfunction "PE15_46") (pintype "passive+no_connect"))
    )
    (net (code "102") (name "unconnected-(IC15-PH1-Pad13)") (class "Default")
      (node (ref "IC15") (pin "13") (pinfunction "PH1_13") (pintype "passive+no_connect"))
    )
    (net (code "103") (name "unconnected-(IC16-NC_1-Pad5)") (class "Default")
      (node (ref "IC16") (pin "5") (pinfunction "NC_1_5") (pintype "passive+no_connect"))
    )
    (net (code "104") (name "unconnected-(IC16-NC_2-Pad7)") (class "Default")
      (node (ref "IC16") (pin "7") (pinfunction "NC_2_7") (pintype "passive+no_connect"))
    )
    (net (code "105") (name "unconnected-(IC17-NC_1-Pad5)") (class "Default")
      (node (ref "IC17") (pin "5") (pinfunction "NC_1_5") (pintype "passive+no_connect"))
    )
    (net (code "106") (name "unconnected-(IC17-NC_2-Pad7)") (class "Default")
      (node (ref "IC17") (pin "7") (pinfunction "NC_2_7") (pintype "passive+no_connect"))
    )
    (net (code "107") (name "unconnected-(IC18-NC_1-Pad1)") (class "Default")
      (node (ref "IC18") (pin "1") (pinfunction "NC_1_1") (pintype "passive+no_connect"))
    )
    (net (code "108") (name "unconnected-(IC18-NC_2-Pad5)") (class "Default")
      (node (ref "IC18") (pin "5") (pinfunction "NC_2_5") (pintype "passive+no_connect"))
    )
    (net (code "109") (name "unconnected-(S1-NC-PadA2)") (class "Default")
      (node (ref "S1") (pin "A2") (pinfunction "NC_A2") (pintype "passive+no_connect"))
    )
    (net (code "110") (name "unconnected-(S1-NC-PadC2)") (class "Default")
      (node (ref "S1") (pin "C2") (pinfunction "NC_C2") (pintype "passive+no_connect"))
    )
    (net (code "111") (name "unconnected-(S2-NC-PadA2)") (class "Default")
      (node (ref "S2") (pin "A2") (pinfunction "NC_A2") (pintype "passive+no_connect"))
    )
    (net (code "112") (name "unconnected-(S2-NC-PadC2)") (class "Default")
      (node (ref "S2") (pin "C2") (pinfunction "NC_C2") (pintype "passive+no_connect"))
    )
    (net (code "113") (name "unconnected-(S3-NC-PadA2)") (class "Default")
      (node (ref "S3") (pin "A2") (pinfunction "NC_A2") (pintype "passive+no_connect"))
    )
    (net (code "114") (name "unconnected-(S3-NC-PadC2)") (class "Default")
      (node (ref "S3") (pin "C2") (pinfunction "NC_C2") (pintype "passive+no_connect"))
    )
    (net (code "115") (name "unconnected-(Y1-N.C.-Pad1)") (class "Default")
      (node (ref "Y1") (pin "1") (pinfunction "N.C._1") (pintype "passive+no_connect"))
    )
  )
)
